# schematic_smart_home.net
KiCad netlist of a schematic drawn in Altium Designer
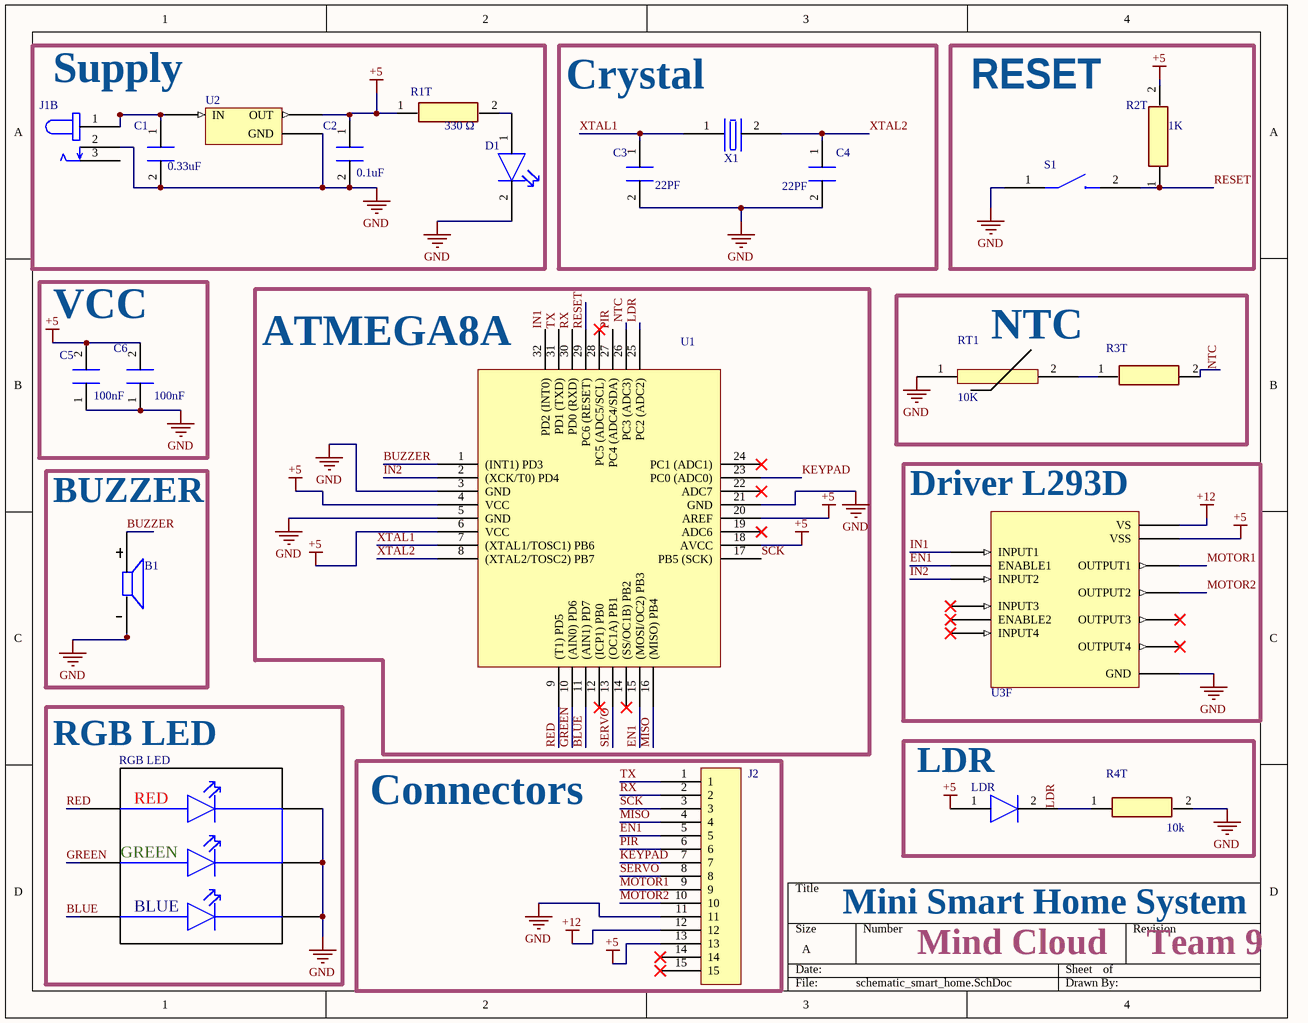
[diagram p0: schematic_smart_home.SchDoc]

(export (version "E")
  (design (tool "Eeschema 10.0.6"))
  (components
    (comp (ref "B1")
      (value "CMT-1271-88-SMT-TR")
      (footprint "PcbLib_buzzer:PCBComponent_1")
      (description "88dB Passive (external drive) Electromagnetic Type 2.4kHz Buzzers ROHS")
      (libsource (lib "Schlib_buzzer") (part "buzzer"))
    )
    (comp (ref "C1")
      (value "0.33uF")
      (footprint "PcbLib_capacitor_1206:PCBComponent_1")
      (description "100V 100nF C0G ±5% 1206 Multilayer Ceramic Capacitors MLCC - SMD/SMT ROHS")
      (fields (field (name "MANUFACTOR PART NUMBER") "GRM31C5C2A104JA01L"))
      (libsource (lib "Schlib_capacitor_1206") (part "capacitor_1206 CODE"))
    )
    (comp (ref "C2")
      (value "0.1uF")
      (footprint "PcbLib_capacitor_1206:PCBComponent_1")
      (description "100V 100nF C0G ±5% 1206 Multilayer Ceramic Capacitors MLCC - SMD/SMT ROHS")
      (fields (field (name "MANUFACTOR PART NUMBER") "GRM31C5C2A104JA01L"))
      (libsource (lib "Schlib_capacitor_1206") (part "capacitor_1206 CODE"))
    )
    (comp (ref "C3")
      (value "22PF")
      (footprint "PcbLib_capacitor_1206:PCBComponent_1")
      (description "100V 100nF C0G ±5% 1206 Multilayer Ceramic Capacitors MLCC - SMD/SMT ROHS")
      (fields (field (name "MANUFACTOR PART NUMBER") "GRM31C5C2A104JA01L"))
      (libsource (lib "Schlib_capacitor_1206") (part "capacitor_1206 CODE"))
    )
    (comp (ref "C4")
      (value "22PF")
      (footprint "PcbLib_capacitor_1206:PCBComponent_1")
      (description "100V 100nF C0G ±5% 1206 Multilayer Ceramic Capacitors MLCC - SMD/SMT ROHS")
      (fields (field (name "MANUFACTOR PART NUMBER") "GRM31C5C2A104JA01L"))
      (libsource (lib "Schlib_capacitor_1206") (part "capacitor_1206 CODE"))
    )
    (comp (ref "C5")
      (value "100nF")
      (footprint "PcbLib_capacitor_1206:PCBComponent_1")
      (description "100V 100nF C0G ±5% 1206 Multilayer Ceramic Capacitors MLCC - SMD/SMT ROHS")
      (fields (field (name "MANUFACTOR PART NUMBER") "GRM31C5C2A104JA01L"))
      (libsource (lib "Schlib_capacitor_1206") (part "capacitor_1206 CODE"))
    )
    (comp (ref "C6")
      (value "100nF")
      (footprint "PcbLib_capacitor_1206:PCBComponent_1")
      (description "100V 100nF C0G ±5% 1206 Multilayer Ceramic Capacitors MLCC - SMD/SMT ROHS")
      (fields (field (name "MANUFACTOR PART NUMBER") "GRM31C5C2A104JA01L"))
      (libsource (lib "Schlib_capacitor_1206") (part "capacitor_1206 CODE"))
    )
    (comp (ref "D1")
      (value "KPT-1608ZGC")
      (footprint "PcbLib_LED 2:PCBComponent_1")
      (description "SMD LED Indication - Discrete ROHS")
      (fields (field (name "MANUFACTURER") "Kingbright"))
      (libsource (lib "Schlib_LED2") (part "LED"))
    )
    (comp (ref "J1")
      (value "PJ-002AH-SMT-TR")
      (footprint "PcbLib_Dc connector:PCBComponent_1")
      (description "SMD DC Power Connectors ROHS")
      (fields (field (name "MANUFACTURER") "CUI"))
      (libsource (lib "Schlib_DC connector") (part "DC connector"))
    )
    (comp (ref "J2")
      (value "connector;str header;single row;.1 cont centers;.095 tail;gold or gtx;36 contact")
      (footprint "Header")
      (fields
        (field (name "MANUFACTURER") "FCI")
        (field (name "MANUFACTURER PART NO.") "68000-236HLF")
        (field (name "CREATED BY") "R Kanjee")
      )
      (libsource (lib "PCB Headers") (part "Single row; PCB headers"))
    )
    (comp (ref "LDR")
      (value "RS1G")
      (footprint "PcbLib_LDR sensor:PCBComponent_1")
      (description "1A Independent Type 1.3V@1A 400V SMA(DO-214AC) Diodes - General Purpose ROHS")
      (libsource (lib "Schlib_LDR sensor") (part "LDR sensor"))
    )
    (comp (ref "R1")
      (value "330 Ω")
      (footprint "PcbLib_resistor:RESC1005X04N")
      (description "500mW Thick Film Resistors 400V ±100ppm/℃ ±1% 100Ω 1210 Chip Resistor - Surface Mount ROHS")
      (fields
        (field (name "MANUFACTURER") "PANASONIC")
        (field (name "MANUFACTURER PART NUMBER") "ERJ-U14F1000U")
      )
      (libsource (lib "Schlib_resistor") (part "Resistor"))
    )
    (comp (ref "R2")
      (value "1K")
      (footprint "PcbLib_resistor:RESC1005X04N")
      (description "500mW Thick Film Resistors 400V ±100ppm/℃ ±1% 100Ω 1210 Chip Resistor - Surface Mount ROHS")
      (fields
        (field (name "MANUFACTURER") "PANASONIC")
        (field (name "MANUFACTURER PART NUMBER") "ERJ-U14F1000U")
      )
      (libsource (lib "") (part "Resistor_1"))
    )
    (comp (ref "R3")
      (value "resistor SMD")
      (footprint "RESC1005X04N")
      (description "500mW Thick Film Resistors 400V ±100ppm/℃ ±1% 100Ω 1210 Chip Resistor - Surface Mount ROHS")
      (fields
        (field (name "MANUFACTURER") "PANASONIC")
        (field (name "MANUFACTURER PART NUMBER") "ERJ-U14F1000U")
      )
      (libsource (lib "Schlib_resistor") (part "Resistor"))
    )
    (comp (ref "R4")
      (value "10k")
      (footprint "RESC1005X04N")
      (description "500mW Thick Film Resistors 400V ±100ppm/℃ ±1% 100Ω 1210 Chip Resistor - Surface Mount ROHS")
      (fields
        (field (name "MANUFACTURER") "PANASONIC")
        (field (name "MANUFACTURER PART NUMBER") "ERJ-U14F1000U")
      )
      (libsource (lib "Schlib_resistor") (part "Resistor"))
    )
    (comp (ref "RGB LED")
      (value "ASMB-TTF2-0B20B")
      (footprint "PcbLib_RGB LED:PCBComponent_1")
      (description "PLCC-6 RGB LEDs ROHS")
      (libsource (lib "Schlib_RGB LED") (part "RGB LED"))
    )
    (comp (ref "RT1")
      (value "10K")
      (footprint "RESC1005X04N")
      (description "10kΩ ±0.5% 3380K ±0.7% 0402 NTC Thermistors ROHS\r\nRecommended For You")
      (fields
        (field (name "MANUFACTURER") "Murata Electronics")
        (field (name "MANUFACTURER PART NUMBER") "NCU15XH103D6SRC")
      )
      (libsource (lib "schli_temperture_sensor_NTC") (part "NTC temperature sensor"))
    )
    (comp (ref "S1")
      (value "TS16-1212-85-BK-100-SMT-TR")
      (footprint "PcbLib_switch:PCBComponent_1")
      (description "50mA Standing paste SPST - normally open 100gf 12V Tactile Switches ROHS")
      (libsource (lib "Schlib_switch") (part "switch"))
    )
    (comp (ref "U1")
      (value "ATMEGA8A-AU_C16190")
      (footprint "TQFP80P900X900X120-32N")
      (description "8KB 1KB FLASH 23 2.7V~5.5V AVR 16MHz TQFP-32(7x7) Microcontrollers (MCU/MPU/SOC) ROHS")
      (fields
        (field (name "MANUFACTURER") "Microchip Tech")
        (field (name "MANUFACTURER PART NUMBER") "ATMEGA8A-AU")
      )
      (libsource (lib "Schematic_library_ATMEGA8A") (part "ATMEGA8A-AU"))
    )
    (comp (ref "U2")
      (value "MC78M05ACDTRKG")
      (footprint "PcbLib_regulator 5v:PCBComponent_1")
      (fields (field (name "MANUFACTURER") "onsemi"))
      (libsource (lib "Schlib_regulator 5v") (part "regulator"))
    )
    (comp (ref "U3")
      (value "Driver L293D")
      (footprint "SOIC127P1030X265-20N")
      (description "SOIC-20-300mil Stepper Motor Driver ROHS")
      (fields
        (field (name "MANUFACTURER") "STMicroelectronics")
        (field (name "MANUFACTURER PART NUMBER") "L293DD013TR")
      )
      (libsource (lib "Schlib_Driver L293D") (part "Driver L293D"))
    )
    (comp (ref "X1")
      (value "16 MHZ")
      (footprint "PcbLib_crystal:PCBComponent_1")
      (description "16MHz ±30ppm ±50ppm HC-49S-SMD Crystals ROHS")
      (libsource (lib "Schlib_crystal") (part "crystal"))
    )
  )
  (nets
    (net (code "1") (name "+5") (class "Default")
      (node (ref "C2") (pin "1") (pinfunction "1_1") (pintype "passive"))
      (node (ref "C5") (pin "2") (pinfunction "2_2") (pintype "passive"))
      (node (ref "C6") (pin "2") (pinfunction "2_2") (pintype "passive"))
      (node (ref "J2") (pin "13") (pinfunction "13_13") (pintype "passive"))
      (node (ref "LDR") (pin "1") (pinfunction "1_1") (pintype "passive"))
      (node (ref "R1") (pin "1") (pinfunction "1_1") (pintype "passive"))
      (node (ref "R2") (pin "2") (pinfunction "2_2") (pintype "passive"))
      (node (ref "U1") (pin "18") (pinfunction "AVCC_18") (pintype "passive"))
      (node (ref "U1") (pin "20") (pinfunction "AREF_20") (pintype "passive"))
      (node (ref "U1") (pin "4") (pinfunction "VCC_4") (pintype "passive"))
      (node (ref "U1") (pin "6") (pinfunction "VCC_6") (pintype "passive"))
      (node (ref "U2") (pin "2") (pinfunction "OUT_2") (pintype "output"))
      (node (ref "U3") (pin "7") (pinfunction "VSS_7") (pintype "passive"))
    )
    (net (code "2") (name "+12") (class "Default")
      (node (ref "J2") (pin "12") (pinfunction "12_12") (pintype "passive"))
      (node (ref "U3") (pin "6") (pinfunction "VS_6") (pintype "passive"))
    )
    (net (code "3") (name "/BLUE") (class "Default")
      (node (ref "RGB LED") (pin "5") (pinfunction "5_5") (pintype "passive"))
      (node (ref "U1") (pin "11") (pinfunction "(AIN1)_PD7_11") (pintype "passive"))
    )
    (net (code "4") (name "/BUZZER") (class "Default")
      (node (ref "B1") (pin "1") (pinfunction "1_1") (pintype "passive"))
      (node (ref "U1") (pin "1") (pinfunction "(INT1)_PD3_1") (pintype "passive"))
    )
    (net (code "5") (name "/EN1") (class "Default")
      (node (ref "J2") (pin "5") (pinfunction "5_5") (pintype "passive"))
      (node (ref "U1") (pin "15") (pinfunction "(MOSI/OC2)_PB3_15") (pintype "passive"))
      (node (ref "U3") (pin "2") (pinfunction "ENABLE1_2") (pintype "passive"))
    )
    (net (code "6") (name "/GREEN") (class "Default")
      (node (ref "RGB LED") (pin "3") (pinfunction "3_3") (pintype "passive"))
      (node (ref "U1") (pin "10") (pinfunction "(AIN0)_PD6_10") (pintype "passive"))
    )
    (net (code "7") (name "/IN1") (class "Default")
      (node (ref "U1") (pin "32") (pinfunction "PD2_(INT0)_32") (pintype "passive"))
      (node (ref "U3") (pin "1") (pinfunction "INPUT1_1") (pintype "input"))
    )
    (net (code "8") (name "/IN2") (class "Default")
      (node (ref "U1") (pin "2") (pinfunction "(XCK/T0)_PD4_2") (pintype "passive"))
      (node (ref "U3") (pin "3") (pinfunction "INPUT2_3") (pintype "input"))
    )
    (net (code "9") (name "/KEYPAD") (class "Default")
      (node (ref "J2") (pin "7") (pinfunction "7_7") (pintype "passive"))
      (node (ref "U1") (pin "23") (pinfunction "PC0_(ADC0)_23") (pintype "passive"))
    )
    (net (code "10") (name "/LDR") (class "Default")
      (node (ref "LDR") (pin "2") (pinfunction "2_2") (pintype "passive"))
      (node (ref "R4") (pin "1") (pinfunction "1_1") (pintype "passive"))
      (node (ref "U1") (pin "25") (pinfunction "PC2_(ADC2)_25") (pintype "passive"))
    )
    (net (code "11") (name "/MISO") (class "Default")
      (node (ref "J2") (pin "4") (pinfunction "4_4") (pintype "passive"))
      (node (ref "U1") (pin "16") (pinfunction "(MISO)_PB4_16") (pintype "passive"))
    )
    (net (code "12") (name "/MOTOR1") (class "Default")
      (node (ref "J2") (pin "9") (pinfunction "9_9") (pintype "passive"))
      (node (ref "U3") (pin "9") (pinfunction "OUTPUT1_9") (pintype "output"))
    )
    (net (code "13") (name "/MOTOR2") (class "Default")
      (node (ref "J2") (pin "10") (pinfunction "10_10") (pintype "passive"))
      (node (ref "U3") (pin "10") (pinfunction "OUTPUT2_10") (pintype "output"))
    )
    (net (code "14") (name "/NTC") (class "Default")
      (node (ref "R3") (pin "2") (pinfunction "2_2") (pintype "passive"))
      (node (ref "U1") (pin "26") (pinfunction "PC3_(ADC3)_26") (pintype "passive"))
    )
    (net (code "15") (name "/PIR") (class "Default")
      (node (ref "J2") (pin "6") (pinfunction "6_6") (pintype "passive"))
      (node (ref "U1") (pin "27") (pinfunction "PC4_(ADC4/SDA)_27") (pintype "passive"))
    )
    (net (code "16") (name "/RED") (class "Default")
      (node (ref "RGB LED") (pin "1") (pinfunction "1_1") (pintype "passive"))
      (node (ref "U1") (pin "9") (pinfunction "(T1)_PD5_9") (pintype "passive"))
    )
    (net (code "17") (name "/RESET") (class "Default")
      (node (ref "R2") (pin "1") (pinfunction "1_1") (pintype "passive"))
      (node (ref "S1") (pin "2") (pinfunction "2_2") (pintype "passive"))
      (node (ref "U1") (pin "29") (pinfunction "PC6_(RESET)_29") (pintype "passive"))
    )
    (net (code "18") (name "/RX") (class "Default")
      (node (ref "J2") (pin "2") (pinfunction "2_2") (pintype "passive"))
      (node (ref "U1") (pin "30") (pinfunction "PD0_(RXD)_30") (pintype "passive"))
    )
    (net (code "19") (name "/SCK") (class "Default")
      (node (ref "J2") (pin "3") (pinfunction "3_3") (pintype "passive"))
      (node (ref "U1") (pin "17") (pinfunction "PB5_(SCK)_17") (pintype "passive"))
    )
    (net (code "20") (name "/SERVO") (class "Default")
      (node (ref "J2") (pin "8") (pinfunction "8_8") (pintype "passive"))
      (node (ref "U1") (pin "13") (pinfunction "(OC1A)_PB1_13") (pintype "passive"))
    )
    (net (code "21") (name "/TX") (class "Default")
      (node (ref "J2") (pin "1") (pinfunction "1_1") (pintype "passive"))
      (node (ref "U1") (pin "31") (pinfunction "PD1_(TXD)_31") (pintype "passive"))
    )
    (net (code "22") (name "/XTAL1") (class "Default")
      (node (ref "C3") (pin "1") (pinfunction "1_1") (pintype "passive"))
      (node (ref "U1") (pin "7") (pinfunction "(XTAL1/TOSC1)_PB6_7") (pintype "passive"))
      (node (ref "X1") (pin "1") (pinfunction "1_1") (pintype "passive"))
    )
    (net (code "23") (name "/XTAL2") (class "Default")
      (node (ref "C4") (pin "1") (pinfunction "1_1") (pintype "passive"))
      (node (ref "U1") (pin "8") (pinfunction "(XTAL2/TOSC2)_PB7_8") (pintype "passive"))
      (node (ref "X1") (pin "2") (pinfunction "2_2") (pintype "passive"))
    )
    (net (code "24") (name "GND") (class "Default")
      (node (ref "B1") (pin "2") (pinfunction "2_2") (pintype "passive"))
      (node (ref "C1") (pin "2") (pinfunction "2_2") (pintype "passive"))
      (node (ref "C2") (pin "2") (pinfunction "2_2") (pintype "passive"))
      (node (ref "C3") (pin "2") (pinfunction "2_2") (pintype "passive"))
      (node (ref "C4") (pin "2") (pinfunction "2_2") (pintype "passive"))
      (node (ref "C5") (pin "1") (pinfunction "1_1") (pintype "passive"))
      (node (ref "C6") (pin "1") (pinfunction "1_1") (pintype "passive"))
      (node (ref "D1") (pin "2") (pinfunction "2_2") (pintype "passive"))
      (node (ref "J1") (pin "2") (pinfunction "2_2") (pintype "passive"))
      (node (ref "J2") (pin "11") (pinfunction "11_11") (pintype "passive"))
      (node (ref "R4") (pin "2") (pinfunction "2_2") (pintype "passive"))
      (node (ref "RGB LED") (pin "2") (pinfunction "2_2") (pintype "passive"))
      (node (ref "RGB LED") (pin "4") (pinfunction "4_4") (pintype "passive"))
      (node (ref "RGB LED") (pin "6") (pinfunction "6_6") (pintype "passive"))
      (node (ref "RT1") (pin "1") (pinfunction "1_1") (pintype "passive"))
      (node (ref "S1") (pin "1") (pinfunction "1_1") (pintype "passive"))
      (node (ref "U1") (pin "21") (pinfunction "GND_21") (pintype "passive"))
      (node (ref "U1") (pin "3") (pinfunction "GND_3") (pintype "passive"))
      (node (ref "U1") (pin "5") (pinfunction "GND_5") (pintype "passive"))
      (node (ref "U2") (pin "3") (pinfunction "GND_3") (pintype "passive"))
      (node (ref "U3") (pin "13") (pinfunction "GND_13") (pintype "passive"))
    )
    (net (code "25") (name "Net-(D1-Pad1)") (class "Default")
      (node (ref "D1") (pin "1") (pinfunction "1_1") (pintype "passive"))
      (node (ref "R1") (pin "2") (pinfunction "2_2") (pintype "passive"))
    )
    (net (code "26") (name "Net-(R3-Pad1)") (class "Default")
      (node (ref "R3") (pin "1") (pinfunction "1_1") (pintype "passive"))
      (node (ref "RT1") (pin "2") (pinfunction "2_2") (pintype "passive"))
    )
    (net (code "27") (name "Net-(U2-IN)") (class "Default")
      (node (ref "C1") (pin "1") (pinfunction "1_1") (pintype "passive"))
      (node (ref "J1") (pin "1") (pinfunction "1_1") (pintype "passive"))
      (node (ref "U2") (pin "1") (pinfunction "IN_1") (pintype "input"))
    )
    (net (code "28") (name "unconnected-(J1-Pad3)") (class "Default")
      (node (ref "J1") (pin "3") (pinfunction "3_3") (pintype "passive"))
    )
    (net (code "29") (name "unconnected-(J2-Pad14)") (class "Default")
      (node (ref "J2") (pin "14") (pinfunction "14_14") (pintype "passive+no_connect"))
    )
    (net (code "30") (name "unconnected-(J2-Pad15)") (class "Default")
      (node (ref "J2") (pin "15") (pinfunction "15_15") (pintype "passive+no_connect"))
    )
    (net (code "31") (name "unconnected-(U1-(ICP1)_PB0-Pad12)") (class "Default")
      (node (ref "U1") (pin "12") (pinfunction "(ICP1)_PB0_12") (pintype "passive+no_connect"))
    )
    (net (code "32") (name "unconnected-(U1-(SS{slash}OC1B)_PB2-Pad14)") (class "Default")
      (node (ref "U1") (pin "14") (pinfunction "(SS/OC1B)_PB2_14") (pintype "passive+no_connect"))
    )
    (net (code "33") (name "unconnected-(U1-ADC6-Pad19)") (class "Default")
      (node (ref "U1") (pin "19") (pinfunction "ADC6_19") (pintype "passive+no_connect"))
    )
    (net (code "34") (name "unconnected-(U1-ADC7-Pad22)") (class "Default")
      (node (ref "U1") (pin "22") (pinfunction "ADC7_22") (pintype "passive+no_connect"))
    )
    (net (code "35") (name "unconnected-(U1-PC1_(ADC1)-Pad24)") (class "Default")
      (node (ref "U1") (pin "24") (pinfunction "PC1_(ADC1)_24") (pintype "passive+no_connect"))
    )
    (net (code "36") (name "unconnected-(U1-PC5_(ADC5{slash}SCL)-Pad28)") (class "Default")
      (node (ref "U1") (pin "28") (pinfunction "PC5_(ADC5/SCL)_28") (pintype "passive+no_connect"))
    )
    (net (code "37") (name "unconnected-(U3F-ENABLE2-Pad5)") (class "Default")
      (node (ref "U3") (pin "5") (pinfunction "ENABLE2_5") (pintype "passive+no_connect"))
    )
    (net (code "38") (name "unconnected-(U3F-INPUT3-Pad4)") (class "Default")
      (node (ref "U3") (pin "4") (pinfunction "INPUT3_4") (pintype "input+no_connect"))
    )
    (net (code "39") (name "unconnected-(U3F-INPUT4-Pad6)") (class "Default")
      (node (ref "U3") (pin "6") (pinfunction "INPUT4_6") (pintype "input+no_connect"))
    )
    (net (code "40") (name "unconnected-(U3F-OUTPUT3-Pad11)") (class "Default")
      (node (ref "U3") (pin "11") (pinfunction "OUTPUT3_11") (pintype "output+no_connect"))
    )
    (net (code "41") (name "unconnected-(U3F-OUTPUT4-Pad12)") (class "Default")
      (node (ref "U3") (pin "12") (pinfunction "OUTPUT4_12") (pintype "output+no_connect"))
    )
  )
)
